# RxPCB_V1-1.net
KiCad netlist of a schematic drawn in EAGLE
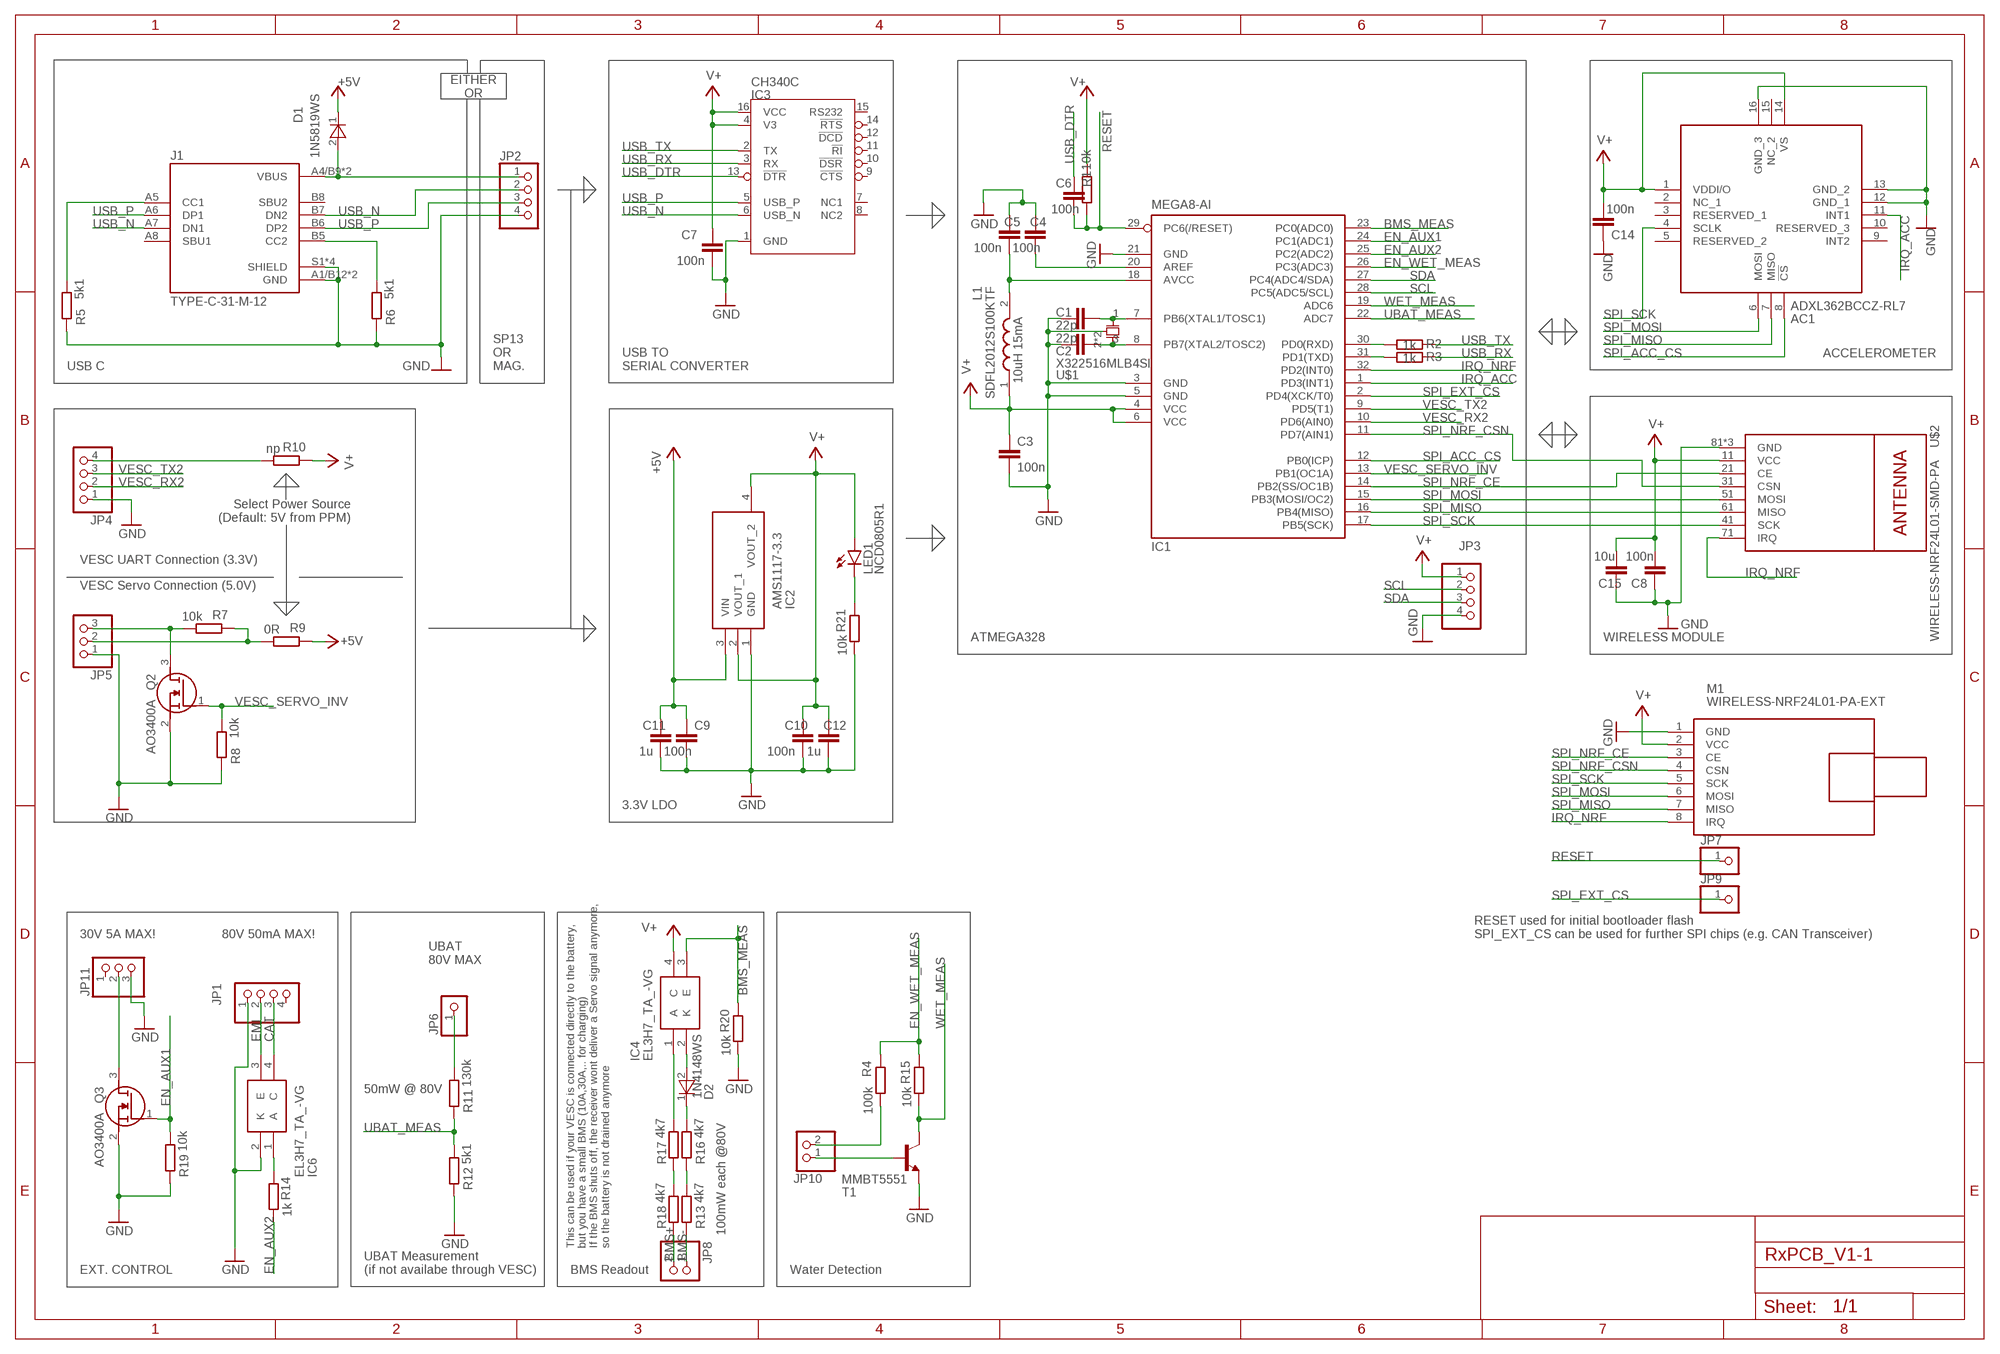
[diagram p0: schematic, sheet 1]

(export (version "E")
  (design (tool "Eeschema 10.0.6"))
  (components
    (comp (ref "AC1")
      (value "ADXL362BCCZ-RL7")
      (footprint "eagle-import:CC-16-4")
      (fields (field (name "MOUSER_PART_NUMBER") "584-ADXL362BCCZ-R7"))
      (libsource (lib "eagle-import") (part "ADXL362BCCZ-RL7"))
    )
    (comp (ref "C1")
      (value "22p")
      (footprint "eagle-import:C0603")
      (libsource (lib "eagle-import") (part "C-EUC0603"))
    )
    (comp (ref "C2")
      (value "22p")
      (footprint "eagle-import:C0603")
      (libsource (lib "eagle-import") (part "C-EUC0603"))
    )
    (comp (ref "C3")
      (value "100n")
      (footprint "eagle-import:C0603")
      (libsource (lib "eagle-import") (part "C-EUC0603"))
    )
    (comp (ref "C4")
      (value "100n")
      (footprint "eagle-import:C0603")
      (libsource (lib "eagle-import") (part "C-EUC0603"))
    )
    (comp (ref "C5")
      (value "100n")
      (footprint "eagle-import:C0603")
      (libsource (lib "eagle-import") (part "C-EUC0603"))
    )
    (comp (ref "C6")
      (value "100n")
      (footprint "eagle-import:C0603")
      (libsource (lib "eagle-import") (part "C-EUC0603"))
    )
    (comp (ref "C7")
      (value "100n")
      (footprint "eagle-import:C0603")
      (libsource (lib "eagle-import") (part "C-EUC0603"))
    )
    (comp (ref "C8")
      (value "100n")
      (footprint "eagle-import:C0603")
      (libsource (lib "eagle-import") (part "C-EUC0603"))
    )
    (comp (ref "C9")
      (value "100n")
      (footprint "eagle-import:C0603")
      (libsource (lib "eagle-import") (part "C-EUC0603"))
    )
    (comp (ref "C10")
      (value "100n")
      (footprint "eagle-import:C0603")
      (libsource (lib "eagle-import") (part "C-EUC0603"))
    )
    (comp (ref "C11")
      (value "1u")
      (footprint "eagle-import:C0603")
      (libsource (lib "eagle-import") (part "C-EUC0603"))
    )
    (comp (ref "C12")
      (value "1u")
      (footprint "eagle-import:C0603")
      (libsource (lib "eagle-import") (part "C-EUC0603"))
    )
    (comp (ref "C14")
      (value "100n")
      (footprint "eagle-import:C0603")
      (libsource (lib "eagle-import") (part "C-EUC0603"))
    )
    (comp (ref "C15")
      (value "10u")
      (footprint "eagle-import:C0603")
      (libsource (lib "eagle-import") (part "C-EUC0603"))
    )
    (comp (ref "D1")
      (value "1N5819WS")
      (footprint "eagle-import:SODFL2512X90N")
      (fields
        (field (name "ARROW_PART_NUMBER") "1N4148WS")
        (field (name "MOUSER_PART_NUMBER") "512-1N4148WS")
      )
      (libsource (lib "eagle-import") (part "1N4148WS"))
    )
    (comp (ref "D2")
      (value "1N4148WS")
      (footprint "eagle-import:SODFL2512X90N")
      (fields (field (name "MOUSER_PART_NUMBER") "512-1N4148WS"))
      (libsource (lib "eagle-import") (part "1N4148WS"))
    )
    (comp (ref "IC1")
      (value "MEGA8-AI")
      (footprint "eagle-import:TQFP32-08")
      (fields (field (name "MPN") "ATMEGA8-16AU"))
      (libsource (lib "eagle-import") (part "MEGA8-AI"))
    )
    (comp (ref "IC2")
      (value "AMS1117-3.3")
      (footprint "eagle-import:SOT229P700X180-4N")
      (libsource (lib "eagle-import") (part "AMS1117-3.3"))
    )
    (comp (ref "IC3")
      (value "CH340C")
      (footprint "eagle-import:SOIC16N")
      (libsource (lib "eagle-import") (part "CH340G"))
    )
    (comp (ref "IC4")
      (value "EL3H7_TA_-VG")
      (footprint "eagle-import:SOIC127P700X200-4N")
      (fields
        (field (name "ARROW_PART_NUMBER") "EL3H7(TA)-VG")
        (field (name "MOUSER_PART_NUMBER") "638-EL3H7TAVG")
      )
      (libsource (lib "eagle-import") (part "EL3H7_TA_-VG"))
    )
    (comp (ref "IC6")
      (value "EL3H7_TA_-VG")
      (footprint "eagle-import:SOIC127P700X200-4N")
      (fields
        (field (name "ARROW_PART_NUMBER") "EL3H7(TA)-VG")
        (field (name "MOUSER_PART_NUMBER") "638-EL3H7TAVG")
      )
      (libsource (lib "eagle-import") (part "EL3H7_TA_-VG"))
    )
    (comp (ref "J1")
      (value "TYPE-C-31-M-12")
      (footprint "eagle-import:HRO_TYPE-C-31-M-12")
      (fields (field (name "MF") "HRO Electronics Co., Ltd."))
      (libsource (lib "eagle-import") (part "TYPE-C-31-M-12"))
    )
    (comp (ref "JP1")
      (value "PINHD-1X4")
      (footprint "eagle-import:1X04")
      (libsource (lib "eagle-import") (part "PINHD-1X4"))
    )
    (comp (ref "JP2")
      (value "PINHD-1X4")
      (footprint "eagle-import:1X04")
      (libsource (lib "eagle-import") (part "PINHD-1X4"))
    )
    (comp (ref "JP3")
      (value "PINHD-1X4")
      (footprint "eagle-import:1X04")
      (libsource (lib "eagle-import") (part "PINHD-1X4"))
    )
    (comp (ref "JP4")
      (value "PINHD-1X4")
      (footprint "eagle-import:1X04")
      (libsource (lib "eagle-import") (part "PINHD-1X4"))
    )
    (comp (ref "JP5")
      (value "PINHD-1X3")
      (footprint "eagle-import:1X03")
      (libsource (lib "eagle-import") (part "PINHD-1X3"))
    )
    (comp (ref "JP6")
      (value "PINHD-1X1")
      (footprint "eagle-import:1X01")
      (libsource (lib "eagle-import") (part "PINHD-1X1"))
    )
    (comp (ref "JP7")
      (value "PINHD-1X1")
      (footprint "eagle-import:1X01")
      (libsource (lib "eagle-import") (part "PINHD-1X1"))
    )
    (comp (ref "JP8")
      (value "PINHD-1X2")
      (footprint "eagle-import:1X02")
      (libsource (lib "eagle-import") (part "PINHD-1X2"))
    )
    (comp (ref "JP9")
      (value "PINHD-1X1")
      (footprint "eagle-import:1X01")
      (libsource (lib "eagle-import") (part "PINHD-1X1"))
    )
    (comp (ref "JP10")
      (value "PINHD-1X2")
      (footprint "eagle-import:1X02")
      (libsource (lib "eagle-import") (part "PINHD-1X2"))
    )
    (comp (ref "JP11")
      (value "PINHD-1X3")
      (footprint "eagle-import:1X03")
      (libsource (lib "eagle-import") (part "PINHD-1X3"))
    )
    (comp (ref "L1")
      (value "SDFL2012S100KTF")
      (footprint "eagle-import:INDC2112X105N")
      (fields (field (name "MANUFACTURER_PART_NUMBER") "SDFL2012Q2R7KTF"))
      (libsource (lib "eagle-import") (part "SDFL2012Q2R7KTF"))
    )
    (comp (ref "LED1")
      (value "NCD0805R1")
      (footprint "eagle-import:CHIP-LED0805")
      (libsource (lib "eagle-import") (part "LEDCHIP-LED0805"))
    )
    (comp (ref "M1")
      (value "WIRELESS-NRF24L01-PA-EXT")
      (footprint "eagle-import:WIRELESS-NRF24L01-PA-EXT")
      (libsource (lib "eagle-import") (part "WIRELESS-NRF24L01-PA-EXT"))
    )
    (comp (ref "Q2")
      (value "AO3400A")
      (footprint "eagle-import:SOT95P280X125-3N")
      (libsource (lib "eagle-import") (part "AO3400A"))
    )
    (comp (ref "Q3")
      (value "AO3400A")
      (footprint "eagle-import:SOT95P280X125-3N")
      (libsource (lib "eagle-import") (part "AO3400A"))
    )
    (comp (ref "R1")
      (value "10k")
      (footprint "eagle-import:R0603")
      (libsource (lib "eagle-import") (part "R-EU_R0603"))
    )
    (comp (ref "R2")
      (value "1k")
      (footprint "eagle-import:R0603")
      (libsource (lib "eagle-import") (part "R-EU_R0603"))
    )
    (comp (ref "R3")
      (value "1k")
      (footprint "eagle-import:R0603")
      (libsource (lib "eagle-import") (part "R-EU_R0603"))
    )
    (comp (ref "R4")
      (value "100k")
      (footprint "eagle-import:R0603")
      (libsource (lib "eagle-import") (part "R-EU_R0603"))
    )
    (comp (ref "R5")
      (value "5k1")
      (footprint "eagle-import:R0603")
      (libsource (lib "eagle-import") (part "R-EU_R0603"))
    )
    (comp (ref "R6")
      (value "5k1")
      (footprint "eagle-import:R0603")
      (libsource (lib "eagle-import") (part "R-EU_R0603"))
    )
    (comp (ref "R7")
      (value "10k")
      (footprint "eagle-import:R0603")
      (libsource (lib "eagle-import") (part "R-EU_R0603"))
    )
    (comp (ref "R8")
      (value "10k")
      (footprint "eagle-import:R0603")
      (libsource (lib "eagle-import") (part "R-EU_R0603"))
    )
    (comp (ref "R9")
      (value "0R")
      (footprint "eagle-import:R0603")
      (libsource (lib "eagle-import") (part "R-EU_R0603"))
    )
    (comp (ref "R10")
      (value "np")
      (footprint "eagle-import:R0603")
      (libsource (lib "eagle-import") (part "R-EU_R0603"))
    )
    (comp (ref "R11")
      (value "130k")
      (footprint "eagle-import:R0603")
      (libsource (lib "eagle-import") (part "R-EU_R0603"))
    )
    (comp (ref "R12")
      (value "5k1")
      (footprint "eagle-import:R0603")
      (libsource (lib "eagle-import") (part "R-EU_R0603"))
    )
    (comp (ref "R13")
      (value "4k7")
      (footprint "eagle-import:R0603")
      (libsource (lib "eagle-import") (part "R-EU_R0603"))
    )
    (comp (ref "R14")
      (value "1k")
      (footprint "eagle-import:R0603")
      (libsource (lib "eagle-import") (part "R-EU_R0603"))
    )
    (comp (ref "R15")
      (value "10k")
      (footprint "eagle-import:R0603")
      (libsource (lib "eagle-import") (part "R-EU_R0603"))
    )
    (comp (ref "R16")
      (value "4k7")
      (footprint "eagle-import:R0603")
      (libsource (lib "eagle-import") (part "R-EU_R0603"))
    )
    (comp (ref "R17")
      (value "4k7")
      (footprint "eagle-import:R0603")
      (libsource (lib "eagle-import") (part "R-EU_R0603"))
    )
    (comp (ref "R18")
      (value "4k7")
      (footprint "eagle-import:R0603")
      (libsource (lib "eagle-import") (part "R-EU_R0603"))
    )
    (comp (ref "R19")
      (value "10k")
      (footprint "eagle-import:R0603")
      (libsource (lib "eagle-import") (part "R-EU_R0603"))
    )
    (comp (ref "R20")
      (value "10k")
      (footprint "eagle-import:R0603")
      (libsource (lib "eagle-import") (part "R-EU_R0603"))
    )
    (comp (ref "R21")
      (value "10k")
      (footprint "eagle-import:R0603")
      (libsource (lib "eagle-import") (part "R-EU_R0603"))
    )
    (comp (ref "T1")
      (value "MMBT5551")
      (footprint "eagle-import:SOT23-BEC")
      (libsource (lib "eagle-import") (part "-NPN-SOT23-BECBC847B"))
    )
    (comp (ref "U$1")
      (value "X322516MLB4SI")
      (footprint "eagle-import:X322516MLB4SI")
      (libsource (lib "eagle-import") (part "X322516_BETTER"))
    )
    (comp (ref "U$2")
      (value "WIRELESS-NRF24L01-SMD-PA")
      (footprint "eagle-import:WIRELESS-NRF24L01_SMD_PA")
      (libsource (lib "eagle-import") (part "WIRELESS-NRF24L01-SMD-PA"))
    )
  )
  (nets
    (net (code "1") (name "+5V") (class "Default")
      (node (ref "C11") (pin "1") (pinfunction "1_1") (pintype "passive"))
      (node (ref "C9") (pin "1") (pinfunction "1_1") (pintype "passive"))
      (node (ref "D1") (pin "1") (pinfunction "K_1") (pintype "bidirectional"))
      (node (ref "IC2") (pin "3") (pinfunction "VIN_3") (pintype "bidirectional"))
      (node (ref "R9") (pin "1") (pinfunction "1_1") (pintype "passive"))
    )
    (net (code "2") (name "/BMS+") (class "Default")
      (node (ref "JP8") (pin "2") (pinfunction "2_2") (pintype "passive"))
      (node (ref "R18") (pin "1") (pinfunction "1_1") (pintype "passive"))
    )
    (net (code "3") (name "/BMS-") (class "Default")
      (node (ref "JP8") (pin "1") (pinfunction "1_1") (pintype "passive"))
      (node (ref "R13") (pin "1") (pinfunction "1_1") (pintype "passive"))
    )
    (net (code "4") (name "/BMS_MEAS") (class "Default")
      (node (ref "IC1") (pin "23") (pinfunction "PC0(ADC0)_23") (pintype "bidirectional"))
      (node (ref "IC4") (pin "3") (pinfunction "E_3") (pintype "bidirectional"))
      (node (ref "R20") (pin "1") (pinfunction "1_1") (pintype "passive"))
    )
    (net (code "5") (name "/CAT") (class "Default")
      (node (ref "IC6") (pin "4") (pinfunction "C_4") (pintype "bidirectional"))
      (node (ref "JP1") (pin "3") (pinfunction "3_3") (pintype "passive"))
    )
    (net (code "6") (name "/EMI") (class "Default")
      (node (ref "IC6") (pin "3") (pinfunction "E_3") (pintype "bidirectional"))
      (node (ref "JP1") (pin "2") (pinfunction "2_2") (pintype "passive"))
    )
    (net (code "7") (name "/EN_AUX1") (class "Default")
      (node (ref "IC1") (pin "24") (pinfunction "PC1(ADC1)_24") (pintype "bidirectional"))
      (node (ref "Q3") (pin "1") (pinfunction "G_1") (pintype "bidirectional"))
      (node (ref "R19") (pin "2") (pinfunction "2_2") (pintype "passive"))
    )
    (net (code "8") (name "/EN_AUX2") (class "Default")
      (node (ref "IC1") (pin "25") (pinfunction "PC2(ADC2)_25") (pintype "bidirectional"))
      (node (ref "R14") (pin "2") (pinfunction "2_2") (pintype "passive"))
    )
    (net (code "9") (name "/EN_WET_MEAS") (class "Default")
      (node (ref "IC1") (pin "26") (pinfunction "PC3(ADC3)_26") (pintype "bidirectional"))
      (node (ref "R15") (pin "1") (pinfunction "1_1") (pintype "passive"))
      (node (ref "R4") (pin "1") (pinfunction "1_1") (pintype "passive"))
    )
    (net (code "10") (name "/IRQ_ACC") (class "Default")
      (node (ref "AC1") (pin "11") (pinfunction "INT1_11") (pintype "input"))
      (node (ref "IC1") (pin "1") (pinfunction "PD3(INT1)_1") (pintype "bidirectional"))
    )
    (net (code "11") (name "/IRQ_NRF") (class "Default")
      (node (ref "IC1") (pin "32") (pinfunction "PD2(INT0)_32") (pintype "bidirectional"))
      (node (ref "M1") (pin "8") (pinfunction "IRQ_8") (pintype "bidirectional"))
      (node (ref "U$2") (pin "71") (pinfunction "IRQ_71") (pintype "bidirectional"))
    )
    (net (code "12") (name "/RESET") (class "Default")
      (node (ref "C6") (pin "2") (pinfunction "2_2") (pintype "passive"))
      (node (ref "IC1") (pin "29") (pinfunction "PC6(/RESET)_29") (pintype "bidirectional"))
      (node (ref "JP7") (pin "1") (pinfunction "1_1") (pintype "passive"))
      (node (ref "R1") (pin "1") (pinfunction "1_1") (pintype "passive"))
    )
    (net (code "13") (name "/SCL") (class "Default")
      (node (ref "IC1") (pin "28") (pinfunction "PC5(ADC5/SCL)_28") (pintype "bidirectional"))
      (node (ref "JP3") (pin "2") (pinfunction "2_2") (pintype "passive"))
    )
    (net (code "14") (name "/SDA") (class "Default")
      (node (ref "IC1") (pin "27") (pinfunction "PC4(ADC4/SDA)_27") (pintype "bidirectional"))
      (node (ref "JP3") (pin "3") (pinfunction "3_3") (pintype "passive"))
    )
    (net (code "15") (name "/SPI_ACC_CS") (class "Default")
      (node (ref "AC1") (pin "8") (pinfunction "~{CS}_8") (pintype "input"))
      (node (ref "IC1") (pin "12") (pinfunction "PB0(ICP)_12") (pintype "bidirectional"))
    )
    (net (code "16") (name "/SPI_EXT_CS") (class "Default")
      (node (ref "IC1") (pin "2") (pinfunction "PD4(XCK/T0)_2") (pintype "bidirectional"))
      (node (ref "JP9") (pin "1") (pinfunction "1_1") (pintype "passive"))
    )
    (net (code "17") (name "/SPI_MISO") (class "Default")
      (node (ref "AC1") (pin "7") (pinfunction "MISO_7") (pintype "bidirectional"))
      (node (ref "IC1") (pin "16") (pinfunction "PB4(MISO)_16") (pintype "bidirectional"))
      (node (ref "M1") (pin "7") (pinfunction "MISO_7") (pintype "bidirectional"))
      (node (ref "U$2") (pin "61") (pinfunction "MISO_61") (pintype "bidirectional"))
    )
    (net (code "18") (name "/SPI_MOSI") (class "Default")
      (node (ref "AC1") (pin "6") (pinfunction "MOSI_6") (pintype "bidirectional"))
      (node (ref "IC1") (pin "15") (pinfunction "PB3(MOSI/OC2)_15") (pintype "bidirectional"))
      (node (ref "M1") (pin "6") (pinfunction "MOSI_6") (pintype "bidirectional"))
      (node (ref "U$2") (pin "51") (pinfunction "MOSI_51") (pintype "bidirectional"))
    )
    (net (code "19") (name "/SPI_NRF_CE") (class "Default")
      (node (ref "IC1") (pin "14") (pinfunction "PB2(SS/OC1B)_14") (pintype "bidirectional"))
      (node (ref "M1") (pin "3") (pinfunction "CE_3") (pintype "bidirectional"))
      (node (ref "U$2") (pin "21") (pinfunction "CE_21") (pintype "bidirectional"))
    )
    (net (code "20") (name "/SPI_NRF_CSN") (class "Default")
      (node (ref "IC1") (pin "11") (pinfunction "PD7(AIN1)_11") (pintype "bidirectional"))
      (node (ref "M1") (pin "4") (pinfunction "CSN_4") (pintype "bidirectional"))
      (node (ref "U$2") (pin "31") (pinfunction "CSN_31") (pintype "bidirectional"))
    )
    (net (code "21") (name "/SPI_SCK") (class "Default")
      (node (ref "AC1") (pin "4") (pinfunction "SCLK_4") (pintype "input"))
      (node (ref "IC1") (pin "17") (pinfunction "PB5(SCK)_17") (pintype "bidirectional"))
      (node (ref "M1") (pin "5") (pinfunction "SCK_5") (pintype "bidirectional"))
      (node (ref "U$2") (pin "41") (pinfunction "SCK_41") (pintype "bidirectional"))
    )
    (net (code "22") (name "/UBAT_MEAS") (class "Default")
      (node (ref "IC1") (pin "22") (pinfunction "ADC7_22") (pintype "bidirectional"))
      (node (ref "R11") (pin "1") (pinfunction "1_1") (pintype "passive"))
      (node (ref "R12") (pin "2") (pinfunction "2_2") (pintype "passive"))
    )
    (net (code "23") (name "/USB_DTR") (class "Default")
      (node (ref "C6") (pin "1") (pinfunction "1_1") (pintype "passive"))
      (node (ref "IC3") (pin "13") (pinfunction "~{DTR}_13") (pintype "output"))
    )
    (net (code "24") (name "/USB_N") (class "Default")
      (node (ref "IC3") (pin "6") (pinfunction "USB_N_6") (pintype "bidirectional"))
      (node (ref "J1") (pin "A7") (pinfunction "DN1_A7") (pintype "bidirectional"))
      (node (ref "J1") (pin "B7") (pinfunction "DN2_B7") (pintype "bidirectional"))
      (node (ref "JP2") (pin "2") (pinfunction "2_2") (pintype "passive"))
    )
    (net (code "25") (name "/USB_P") (class "Default")
      (node (ref "IC3") (pin "5") (pinfunction "USB_P_5") (pintype "bidirectional"))
      (node (ref "J1") (pin "A6") (pinfunction "DP1_A6") (pintype "bidirectional"))
      (node (ref "J1") (pin "B6") (pinfunction "DP2_B6") (pintype "bidirectional"))
      (node (ref "JP2") (pin "3") (pinfunction "3_3") (pintype "passive"))
    )
    (net (code "26") (name "/USB_RX") (class "Default")
      (node (ref "IC3") (pin "3") (pinfunction "RX_3") (pintype "input"))
      (node (ref "R3") (pin "1") (pinfunction "1_1") (pintype "passive"))
    )
    (net (code "27") (name "/USB_TX") (class "Default")
      (node (ref "IC3") (pin "2") (pinfunction "TX_2") (pintype "output"))
      (node (ref "R2") (pin "1") (pinfunction "1_1") (pintype "passive"))
    )
    (net (code "28") (name "/VESC_RX2") (class "Default")
      (node (ref "IC1") (pin "10") (pinfunction "PD6(AIN0)_10") (pintype "bidirectional"))
      (node (ref "JP4") (pin "2") (pinfunction "2_2") (pintype "passive"))
    )
    (net (code "29") (name "/VESC_SERVO_INV") (class "Default")
      (node (ref "IC1") (pin "13") (pinfunction "PB1(OC1A)_13") (pintype "bidirectional"))
      (node (ref "Q2") (pin "1") (pinfunction "G_1") (pintype "bidirectional"))
      (node (ref "R8") (pin "2") (pinfunction "2_2") (pintype "passive"))
    )
    (net (code "30") (name "/VESC_TX2") (class "Default")
      (node (ref "IC1") (pin "9") (pinfunction "PD5(T1)_9") (pintype "bidirectional"))
      (node (ref "JP4") (pin "3") (pinfunction "3_3") (pintype "passive"))
    )
    (net (code "31") (name "/WET_MEAS") (class "Default")
      (node (ref "IC1") (pin "19") (pinfunction "ADC6_19") (pintype "bidirectional"))
      (node (ref "R15") (pin "2") (pinfunction "2_2") (pintype "passive"))
      (node (ref "T1") (pin "C") (pinfunction "C_C") (pintype "passive"))
    )
    (net (code "32") (name "GND") (class "Default")
      (node (ref "AC1") (pin "12") (pinfunction "GND_1_12") (pintype "power_in"))
      (node (ref "AC1") (pin "13") (pinfunction "GND_2_13") (pintype "power_in"))
      (node (ref "AC1") (pin "16") (pinfunction "GND_3_16") (pintype "power_in"))
      (node (ref "C1") (pin "2") (pinfunction "2_2") (pintype "passive"))
      (node (ref "C10") (pin "2") (pinfunction "2_2") (pintype "passive"))
      (node (ref "C11") (pin "2") (pinfunction "2_2") (pintype "passive"))
      (node (ref "C12") (pin "2") (pinfunction "2_2") (pintype "passive"))
      (node (ref "C14") (pin "1") (pinfunction "1_1") (pintype "passive"))
      (node (ref "C15") (pin "2") (pinfunction "2_2") (pintype "passive"))
      (node (ref "C2") (pin "2") (pinfunction "2_2") (pintype "passive"))
      (node (ref "C3") (pin "2") (pinfunction "2_2") (pintype "passive"))
      (node (ref "C4") (pin "1") (pinfunction "1_1") (pintype "passive"))
      (node (ref "C5") (pin "1") (pinfunction "1_1") (pintype "passive"))
      (node (ref "C7") (pin "2") (pinfunction "2_2") (pintype "passive"))
      (node (ref "C8") (pin "1") (pinfunction "1_1") (pintype "passive"))
      (node (ref "C9") (pin "2") (pinfunction "2_2") (pintype "passive"))
      (node (ref "IC1") (pin "21") (pinfunction "GND_21") (pintype "power_in"))
      (node (ref "IC1") (pin "3") (pinfunction "GND_3") (pintype "power_in"))
      (node (ref "IC1") (pin "5") (pinfunction "GND_5") (pintype "power_in"))
      (node (ref "IC2") (pin "1") (pinfunction "GND_1") (pintype "bidirectional"))
      (node (ref "IC3") (pin "1") (pinfunction "GND_1") (pintype "input"))
      (node (ref "IC6") (pin "2") (pinfunction "K_2") (pintype "bidirectional"))
      (node (ref "J1") (pin "A1/B12") (pinfunction "GND_A1/B12") (pintype "power_in"))
      (node (ref "J1") (pin "B1/A12") (pinfunction "GND_B1/A12") (pintype "power_in"))
      (node (ref "J1") (pin "S1") (pinfunction "SHIELD_S1") (pintype "passive"))
      (node (ref "J1") (pin "S2") (pinfunction "SHIELD_S2") (pintype "passive"))
      (node (ref "J1") (pin "S3") (pinfunction "SHIELD_S3") (pintype "passive"))
      (node (ref "J1") (pin "S4") (pinfunction "SHIELD_S4") (pintype "passive"))
      (node (ref "JP1") (pin "1") (pinfunction "1_1") (pintype "passive"))
      (node (ref "JP11") (pin "3") (pinfunction "3_3") (pintype "passive"))
      (node (ref "JP2") (pin "4") (pinfunction "4_4") (pintype "passive"))
      (node (ref "JP3") (pin "4") (pinfunction "4_4") (pintype "passive"))
      (node (ref "JP4") (pin "1") (pinfunction "1_1") (pintype "passive"))
      (node (ref "JP5") (pin "1") (pinfunction "1_1") (pintype "passive"))
      (node (ref "M1") (pin "1") (pinfunction "GND_1") (pintype "power_in"))
      (node (ref "Q2") (pin "2") (pinfunction "S_2") (pintype "bidirectional"))
      (node (ref "Q3") (pin "2") (pinfunction "S_2") (pintype "bidirectional"))
      (node (ref "R12") (pin "1") (pinfunction "1_1") (pintype "passive"))
      (node (ref "R19") (pin "1") (pinfunction "1_1") (pintype "passive"))
      (node (ref "R20") (pin "2") (pinfunction "2_2") (pintype "passive"))
      (node (ref "R21") (pin "2") (pinfunction "2_2") (pintype "passive"))
      (node (ref "R5") (pin "1") (pinfunction "1_1") (pintype "passive"))
      (node (ref "R6") (pin "1") (pinfunction "1_1") (pintype "passive"))
      (node (ref "R8") (pin "1") (pinfunction "1_1") (pintype "passive"))
      (node (ref "T1") (pin "E") (pinfunction "E_E") (pintype "passive"))
      (node (ref "U$1") (pin "2") (pinfunction "G_2") (pintype "bidirectional"))
      (node (ref "U$1") (pin "4") (pinfunction "G_4") (pintype "bidirectional"))
      (node (ref "U$2") (pin "81") (pinfunction "GND_81") (pintype "power_in"))
      (node (ref "U$2") (pin "P1") (pinfunction "GND_P1") (pintype "power_in"))
      (node (ref "U$2") (pin "P2") (pinfunction "GND_P2") (pintype "power_in"))
    )
    (net (code "33") (name "Net-(D1-A)") (class "Default")
      (node (ref "D1") (pin "2") (pinfunction "A_2") (pintype "bidirectional"))
      (node (ref "J1") (pin "A4/B9") (pinfunction "VBUS_A4/B9") (pintype "power_in"))
      (node (ref "J1") (pin "B4/A9") (pinfunction "VBUS_B4/A9") (pintype "power_in"))
      (node (ref "JP2") (pin "1") (pinfunction "1_1") (pintype "passive"))
    )
    (net (code "34") (name "Net-(D2-A)") (class "Default")
      (node (ref "D2") (pin "2") (pinfunction "A_2") (pintype "bidirectional"))
      (node (ref "IC4") (pin "2") (pinfunction "K_2") (pintype "bidirectional"))
    )
    (net (code "35") (name "Net-(D2-K)") (class "Default")
      (node (ref "D2") (pin "1") (pinfunction "K_1") (pintype "bidirectional"))
      (node (ref "R16") (pin "2") (pinfunction "2_2") (pintype "passive"))
    )
    (net (code "36") (name "Net-(IC1-AREF)") (class "Default")
      (node (ref "C4") (pin "2") (pinfunction "2_2") (pintype "passive"))
      (node (ref "IC1") (pin "20") (pinfunction "AREF_20") (pintype "passive"))
    )
    (net (code "37") (name "Net-(IC1-AVCC)") (class "Default")
      (node (ref "C5") (pin "2") (pinfunction "2_2") (pintype "passive"))
      (node (ref "IC1") (pin "18") (pinfunction "AVCC_18") (pintype "power_in"))
      (node (ref "L1") (pin "2") (pinfunction "2_2") (pintype "bidirectional"))
    )
    (net (code "38") (name "Net-(IC1-PB6(XTAL1{slash}TOSC1))") (class "Default")
      (node (ref "C1") (pin "1") (pinfunction "1_1") (pintype "passive"))
      (node (ref "IC1") (pin "7") (pinfunction "PB6(XTAL1/TOSC1)_7") (pintype "bidirectional"))
      (node (ref "U$1") (pin "1") (pinfunction "X1_1") (pintype "bidirectional"))
    )
    (net (code "39") (name "Net-(IC1-PB7(XTAL2{slash}TOSC2))") (class "Default")
      (node (ref "C2") (pin "1") (pinfunction "1_1") (pintype "passive"))
      (node (ref "IC1") (pin "8") (pinfunction "PB7(XTAL2/TOSC2)_8") (pintype "bidirectional"))
      (node (ref "U$1") (pin "3") (pinfunction "X2_3") (pintype "bidirectional"))
    )
    (net (code "40") (name "Net-(IC1-PD0(RXD))") (class "Default")
      (node (ref "IC1") (pin "30") (pinfunction "PD0(RXD)_30") (pintype "bidirectional"))
      (node (ref "R2") (pin "2") (pinfunction "2_2") (pintype "passive"))
    )
    (net (code "41") (name "Net-(IC1-PD1(TXD))") (class "Default")
      (node (ref "IC1") (pin "31") (pinfunction "PD1(TXD)_31") (pintype "bidirectional"))
      (node (ref "R3") (pin "2") (pinfunction "2_2") (pintype "passive"))
    )
    (net (code "42") (name "Net-(IC4-A)") (class "Default")
      (node (ref "IC4") (pin "1") (pinfunction "A_1") (pintype "bidirectional"))
      (node (ref "R17") (pin "2") (pinfunction "2_2") (pintype "passive"))
    )
    (net (code "43") (name "Net-(IC6-A)") (class "Default")
      (node (ref "IC6") (pin "1") (pinfunction "A_1") (pintype "bidirectional"))
      (node (ref "R14") (pin "1") (pinfunction "1_1") (pintype "passive"))
    )
    (net (code "44") (name "Net-(J1-CC1)") (class "Default")
      (node (ref "J1") (pin "A5") (pinfunction "CC1_A5") (pintype "bidirectional"))
      (node (ref "R5") (pin "2") (pinfunction "2_2") (pintype "passive"))
    )
    (net (code "45") (name "Net-(J1-CC2)") (class "Default")
      (node (ref "J1") (pin "B5") (pinfunction "CC2_B5") (pintype "bidirectional"))
      (node (ref "R6") (pin "2") (pinfunction "2_2") (pintype "passive"))
    )
    (net (code "46") (name "Net-(JP4-Pad4)") (class "Default")
      (node (ref "JP4") (pin "4") (pinfunction "4_4") (pintype "passive"))
      (node (ref "R10") (pin "2") (pinfunction "2_2") (pintype "passive"))
    )
    (net (code "47") (name "Net-(JP5-Pad2)") (class "Default")
      (node (ref "JP5") (pin "2") (pinfunction "2_2") (pintype "passive"))
      (node (ref "R7") (pin "1") (pinfunction "1_1") (pintype "passive"))
      (node (ref "R9") (pin "2") (pinfunction "2_2") (pintype "passive"))
    )
    (net (code "48") (name "Net-(JP6-Pad1)") (class "Default")
      (node (ref "JP6") (pin "1") (pinfunction "1_1") (pintype "passive"))
      (node (ref "R11") (pin "2") (pinfunction "2_2") (pintype "passive"))
    )
    (net (code "49") (name "Net-(JP10-Pad1)") (class "Default")
      (node (ref "JP10") (pin "1") (pinfunction "1_1") (pintype "passive"))
      (node (ref "T1") (pin "B") (pinfunction "B_B") (pintype "passive"))
    )
    (net (code "50") (name "Net-(JP10-Pad2)") (class "Default")
      (node (ref "JP10") (pin "2") (pinfunction "2_2") (pintype "passive"))
      (node (ref "R4") (pin "2") (pinfunction "2_2") (pintype "passive"))
    )
    (net (code "51") (name "Net-(LED1-PadC)") (class "Default")
      (node (ref "LED1") (pin "C") (pinfunction "C_C") (pintype "passive"))
      (node (ref "R21") (pin "1") (pinfunction "1_1") (pintype "passive"))
    )
    (net (code "52") (name "Net-(Q2-D)") (class "Default")
      (node (ref "JP5") (pin "3") (pinfunction "3_3") (pintype "passive"))
      (node (ref "Q2") (pin "3") (pinfunction "D_3") (pintype "bidirectional"))
      (node (ref "R7") (pin "2") (pinfunction "2_2") (pintype "passive"))
    )
    (net (code "53") (name "Net-(Q3-D)") (class "Default")
      (node (ref "JP11") (pin "2") (pinfunction "2_2") (pintype "passive"))
      (node (ref "Q3") (pin "3") (pinfunction "D_3") (pintype "bidirectional"))
    )
    (net (code "54") (name "Net-(R13-Pad2)") (class "Default")
      (node (ref "R13") (pin "2") (pinfunction "2_2") (pintype "passive"))
      (node (ref "R16") (pin "1") (pinfunction "1_1") (pintype "passive"))
    )
    (net (code "55") (name "Net-(R17-Pad1)") (class "Default")
      (node (ref "R17") (pin "1") (pinfunction "1_1") (pintype "passive"))
      (node (ref "R18") (pin "2") (pinfunction "2_2") (pintype "passive"))
    )
    (net (code "56") (name "V+") (class "Default")
      (node (ref "AC1") (pin "1") (pinfunction "VDDI/O_1") (pintype "power_in"))
      (node (ref "AC1") (pin "14") (pinfunction "VS_14") (pintype "bidirectional"))
      (node (ref "C10") (pin "1") (pinfunction "1_1") (pintype "passive"))
      (node (ref "C12") (pin "1") (pinfunction "1_1") (pintype "passive"))
      (node (ref "C14") (pin "2") (pinfunction "2_2") (pintype "passive"))
      (node (ref "C15") (pin "1") (pinfunction "1_1") (pintype "passive"))
      (node (ref "C3") (pin "1") (pinfunction "1_1") (pintype "passive"))
      (node (ref "C7") (pin "1") (pinfunction "1_1") (pintype "passive"))
      (node (ref "C8") (pin "2") (pinfunction "2_2") (pintype "passive"))
      (node (ref "IC1") (pin "4") (pinfunction "VCC_4") (pintype "power_in"))
      (node (ref "IC1") (pin "6") (pinfunction "VCC_6") (pintype "power_in"))
      (node (ref "IC2") (pin "2") (pinfunction "VOUT_1_2") (pintype "bidirectional"))
      (node (ref "IC2") (pin "4") (pinfunction "VOUT_2_4") (pintype "bidirectional"))
      (node (ref "IC3") (pin "16") (pinfunction "VCC_16") (pintype "input"))
      (node (ref "IC3") (pin "4") (pinfunction "V3_4") (pintype "output"))
      (node (ref "IC4") (pin "4") (pinfunction "C_4") (pintype "bidirectional"))
      (node (ref "JP3") (pin "1") (pinfunction "1_1") (pintype "passive"))
      (node (ref "L1") (pin "1") (pinfunction "1_1") (pintype "bidirectional"))
      (node (ref "LED1") (pin "A") (pinfunction "A_A") (pintype "passive"))
      (node (ref "M1") (pin "2") (pinfunction "VCC_2") (pintype "power_in"))
      (node (ref "R1") (pin "2") (pinfunction "2_2") (pintype "passive"))
      (node (ref "R10") (pin "1") (pinfunction "1_1") (pintype "passive"))
      (node (ref "U$2") (pin "11") (pinfunction "VCC_11") (pintype "power_in"))
    )
    (net (code "57") (name "unconnected-(AC1-INT2-Pad9)") (class "Default")
      (node (ref "AC1") (pin "9") (pinfunction "INT2_9") (pintype "input"))
    )
    (net (code "58") (name "unconnected-(AC1-NC_1-Pad2)") (class "Default")
      (node (ref "AC1") (pin "2") (pinfunction "NC_1_2") (pintype "bidirectional"))
    )
    (net (code "59") (name "unconnected-(AC1-NC_2-Pad15)") (class "Default")
      (node (ref "AC1") (pin "15") (pinfunction "NC_2_15") (pintype "bidirectional"))
    )
    (net (code "60") (name "unconnected-(AC1-RESERVED_1-Pad3)") (class "Default")
      (node (ref "AC1") (pin "3") (pinfunction "RESERVED_1_3") (pintype "bidirectional"))
    )
    (net (code "61") (name "unconnected-(AC1-RESERVED_2-Pad5)") (class "Default")
      (node (ref "AC1") (pin "5") (pinfunction "RESERVED_2_5") (pintype "bidirectional"))
    )
    (net (code "62") (name "unconnected-(AC1-RESERVED_3-Pad10)") (class "Default")
      (node (ref "AC1") (pin "10") (pinfunction "RESERVED_3_10") (pintype "bidirectional"))
    )
    (net (code "63") (name "unconnected-(IC3-NC1-Pad7)") (class "Default")
      (node (ref "IC3") (pin "7") (pinfunction "NC1_7") (pintype "no_connect"))
    )
    (net (code "64") (name "unconnected-(IC3-NC2-Pad8)") (class "Default")
      (node (ref "IC3") (pin "8") (pinfunction "NC2_8") (pintype "no_connect"))
    )
    (net (code "65") (name "unconnected-(IC3-RS232-Pad15)") (class "Default")
      (node (ref "IC3") (pin "15") (pinfunction "RS232_15") (pintype "input"))
    )
    (net (code "66") (name "unconnected-(IC3-~{CTS}-Pad9)") (class "Default")
      (node (ref "IC3") (pin "9") (pinfunction "~{CTS}_9") (pintype "input"))
    )
    (net (code "67") (name "unconnected-(IC3-~{DCD}-Pad12)") (class "Default")
      (node (ref "IC3") (pin "12") (pinfunction "~{DCD}_12") (pintype "input"))
    )
    (net (code "68") (name "unconnected-(IC3-~{DSR}-Pad10)") (class "Default")
      (node (ref "IC3") (pin "10") (pinfunction "~{DSR}_10") (pintype "input"))
    )
    (net (code "69") (name "unconnected-(IC3-~{RI}-Pad11)") (class "Default")
      (node (ref "IC3") (pin "11") (pinfunction "~{RI}_11") (pintype "input"))
    )
    (net (code "70") (name "unconnected-(IC3-~{RTS}-Pad14)") (class "Default")
      (node (ref "IC3") (pin "14") (pinfunction "~{RTS}_14") (pintype "output"))
    )
    (net (code "71") (name "unconnected-(J1-SBU1-PadA8)") (class "Default")
      (node (ref "J1") (pin "A8") (pinfunction "SBU1_A8") (pintype "bidirectional"))
    )
    (net (code "72") (name "unconnected-(J1-SBU2-PadB8)") (class "Default")
      (node (ref "J1") (pin "B8") (pinfunction "SBU2_B8") (pintype "bidirectional"))
    )
    (net (code "73") (name "unconnected-(JP1-Pad4)") (class "Default")
      (node (ref "JP1") (pin "4") (pinfunction "4_4") (pintype "passive"))
    )
    (net (code "74") (name "unconnected-(JP11-Pad1)") (class "Default")
      (node (ref "JP11") (pin "1") (pinfunction "1_1") (pintype "passive"))
    )
  )
)
